# electronics_pom.net
KiCad netlist of a schematic drawn in EAGLE
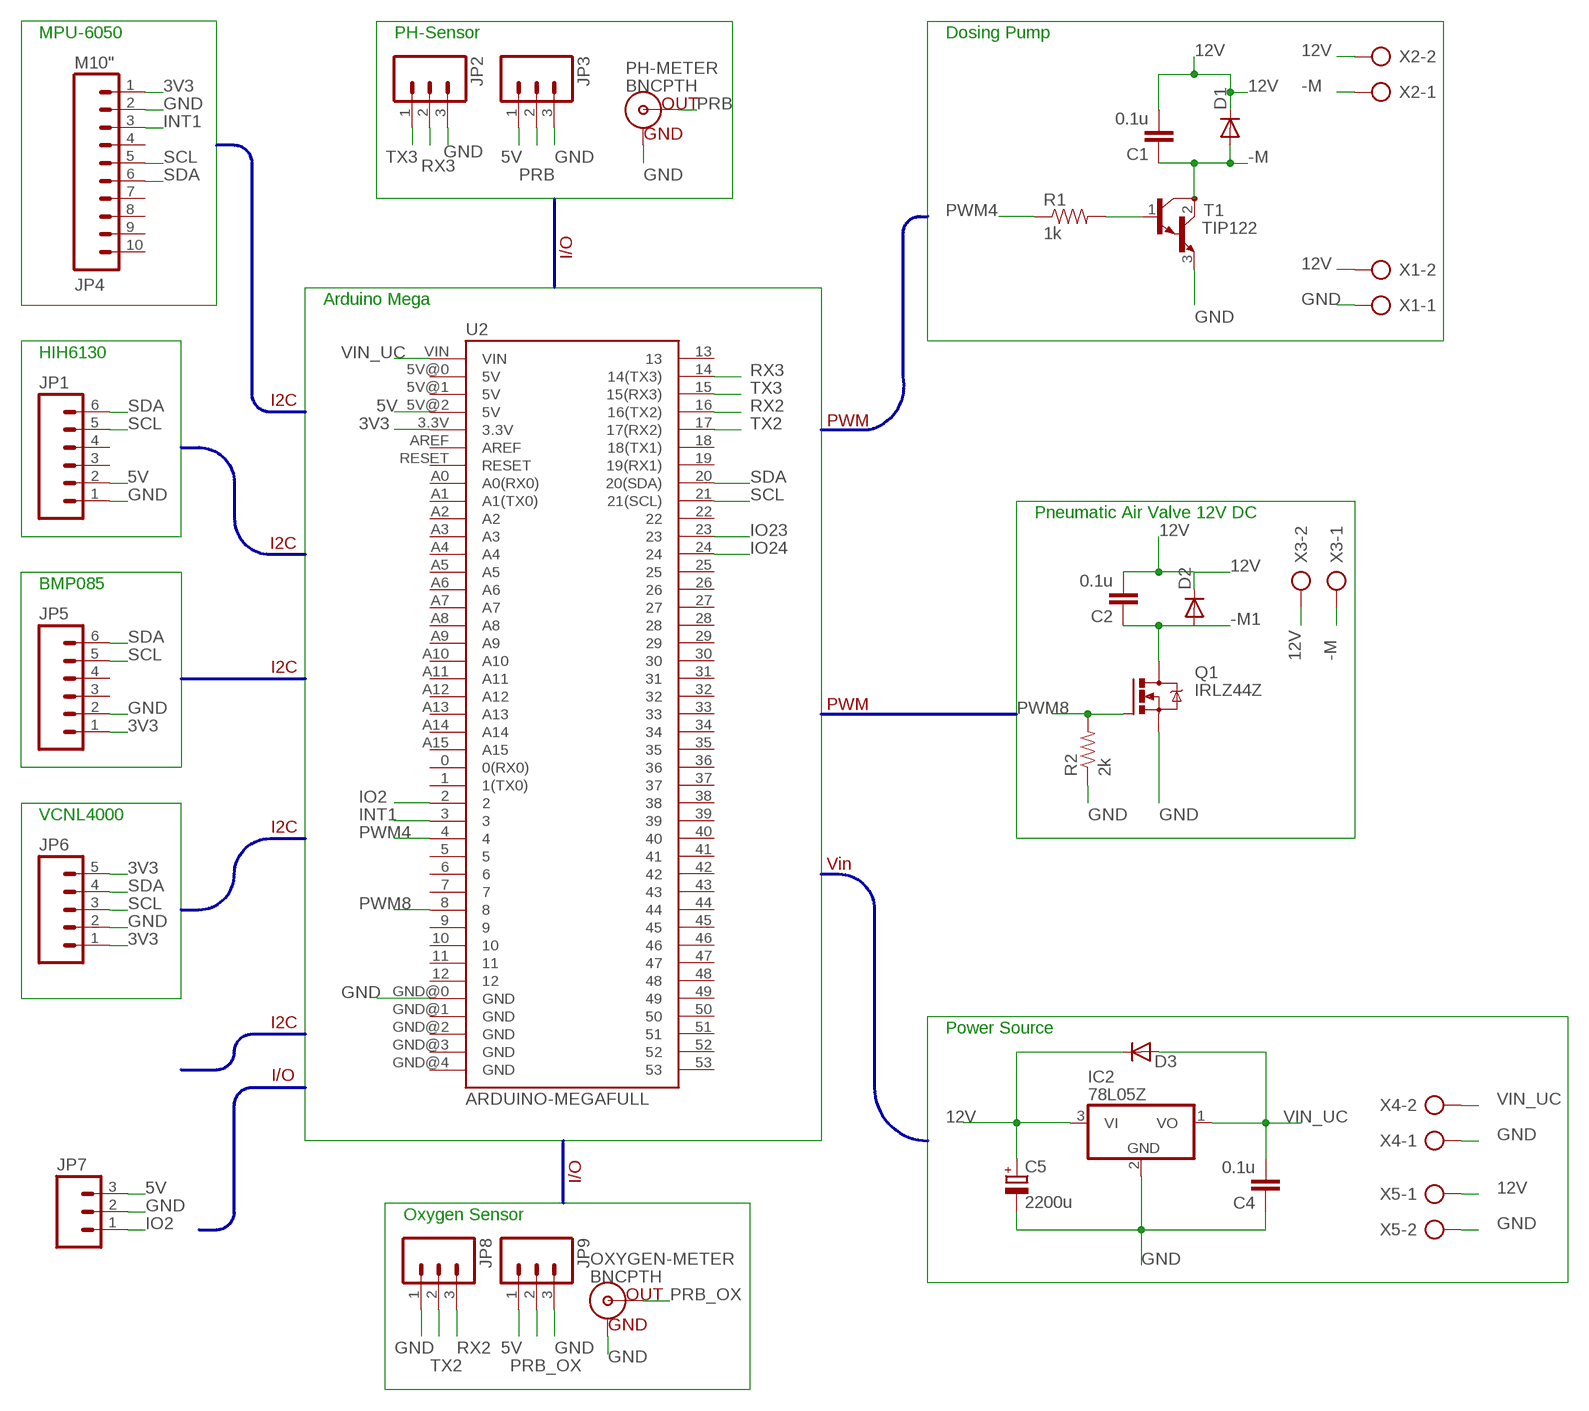
[diagram p0: schematic, sheet 1]

(export (version "E")
  (design (tool "Eeschema 10.0.6"))
  (components
    (comp (ref "C1")
      (value "0.1u")
      (footprint "eagle-import:CAP-PTH-SMALL")
      (libsource (lib "eagle-import") (part "CAPPTH"))
    )
    (comp (ref "C2")
      (value "0.1u")
      (footprint "eagle-import:CAP-PTH-SMALL")
      (libsource (lib "eagle-import") (part "CAPPTH"))
    )
    (comp (ref "C4")
      (value "0.1u")
      (footprint "eagle-import:CAP-PTH-SMALL")
      (libsource (lib "eagle-import") (part "CAPPTH"))
    )
    (comp (ref "C5")
      (value "2200u")
      (footprint "eagle-import:E5-13")
      (libsource (lib "eagle-import") (part "CPOL-EUE5-13"))
    )
    (comp (ref "D1")
      (value "DIODEPTH")
      (footprint "eagle-import:DIODE-1N4001")
      (libsource (lib "eagle-import") (part "DIODEPTH"))
    )
    (comp (ref "D2")
      (value "DIODEPTH")
      (footprint "eagle-import:DIODE-1N4001")
      (libsource (lib "eagle-import") (part "DIODEPTH"))
    )
    (comp (ref "D3")
      (value "DIODEPTH")
      (footprint "eagle-import:DIODE-1N4001")
      (libsource (lib "eagle-import") (part "DIODEPTH"))
    )
    (comp (ref "IC2")
      (value "78L05Z")
      (footprint "eagle-import:TO92")
      (libsource (lib "eagle-import") (part "78ZL05"))
    )
    (comp (ref "JP1")
      (value "M06LONGPADS")
      (footprint "eagle-import:1X06_LONGPADS")
      (libsource (lib "eagle-import") (part "M06LONGPADS"))
    )
    (comp (ref "JP2")
      (value "M03LONGPADS")
      (footprint "eagle-import:1X03_LONGPADS")
      (libsource (lib "eagle-import") (part "M03LONGPADS"))
    )
    (comp (ref "JP3")
      (value "M03LONGPADS")
      (footprint "eagle-import:1X03_LONGPADS")
      (libsource (lib "eagle-import") (part "M03LONGPADS"))
    )
    (comp (ref "JP4")
      (value "M10\"")
      (footprint "eagle-import:1X10")
      (libsource (lib "eagle-import") (part "M10{dblquote}"))
    )
    (comp (ref "JP5")
      (value "M06LONGPADS")
      (footprint "eagle-import:1X06_LONGPADS")
      (libsource (lib "eagle-import") (part "M06LONGPADS"))
    )
    (comp (ref "JP6")
      (value "M05PTH_LONGPADS")
      (footprint "eagle-import:1X05_LONGPADS")
      (libsource (lib "eagle-import") (part "M05PTH_LONGPADS"))
    )
    (comp (ref "JP7")
      (value "M03LONGPADS")
      (footprint "eagle-import:1X03_LONGPADS")
      (libsource (lib "eagle-import") (part "M03LONGPADS"))
    )
    (comp (ref "JP8")
      (value "M03LONGPADS")
      (footprint "eagle-import:1X03_LONGPADS")
      (libsource (lib "eagle-import") (part "M03LONGPADS"))
    )
    (comp (ref "JP9")
      (value "M03LONGPADS")
      (footprint "eagle-import:1X03_LONGPADS")
      (libsource (lib "eagle-import") (part "M03LONGPADS"))
    )
    (comp (ref "OXYGEN-METER")
      (value "BNCPTH")
      (footprint "eagle-import:BNC")
      (libsource (lib "eagle-import") (part "BNCPTH"))
    )
    (comp (ref "PH-METER")
      (value "BNCPTH")
      (footprint "eagle-import:BNC")
      (libsource (lib "eagle-import") (part "BNCPTH"))
    )
    (comp (ref "Q1")
      (value "IRLZ44Z")
      (footprint "eagle-import:TO220BH")
      (libsource (lib "eagle-import") (part "IRLZ44Z"))
    )
    (comp (ref "R1")
      (value "1k")
      (footprint "eagle-import:AXIAL-0.4")
      (libsource (lib "eagle-import") (part "RESISTORPTH-1/4W"))
    )
    (comp (ref "R2")
      (value "2k")
      (footprint "eagle-import:AXIAL-0.4")
      (libsource (lib "eagle-import") (part "RESISTORPTH-1/4W"))
    )
    (comp (ref "T1")
      (value "TIP122")
      (footprint "eagle-import:TO220")
      (libsource (lib "eagle-import") (part "TIP122"))
    )
    (comp (ref "U2")
      (value "ARDUINO-MEGAFULL")
      (footprint "eagle-import:ARDUINO_MEGA")
      (libsource (lib "eagle-import") (part "ARDUINO-MEGAFULL"))
    )
    (comp (ref "X1")
      (value "AK500/2")
      (footprint "eagle-import:AK500_2")
      (libsource (lib "eagle-import") (part "AK500/2"))
    )
    (comp (ref "X2")
      (value "AK500/2")
      (footprint "eagle-import:AK500_2")
      (libsource (lib "eagle-import") (part "AK500/2"))
    )
    (comp (ref "X3")
      (value "AK500/2")
      (footprint "eagle-import:AK500_2")
      (libsource (lib "eagle-import") (part "AK500/2"))
    )
    (comp (ref "X4")
      (value "AK500/2")
      (footprint "eagle-import:AK500_2")
      (libsource (lib "eagle-import") (part "AK500/2"))
    )
    (comp (ref "X5")
      (value "AK500/2")
      (footprint "eagle-import:AK500_2")
      (libsource (lib "eagle-import") (part "AK500/2"))
    )
  )
  (nets
    (net (code "1") (name "/-M") (class "Default")
      (node (ref "C1") (pin "1") (pinfunction "1_1") (pintype "passive"))
      (node (ref "D1") (pin "A") (pinfunction "A_A") (pintype "passive"))
      (node (ref "T1") (pin "2") (pinfunction "C_2") (pintype "passive"))
      (node (ref "X2") (pin "1") (pinfunction "KL_1") (pintype "passive"))
      (node (ref "X3") (pin "1") (pinfunction "KL_1") (pintype "passive"))
    )
    (net (code "2") (name "/-M1") (class "Default")
      (node (ref "C2") (pin "1") (pinfunction "1_1") (pintype "passive"))
      (node (ref "D2") (pin "A") (pinfunction "A_A") (pintype "passive"))
      (node (ref "Q1") (pin "D") (pinfunction "D_D") (pintype "passive"))
    )
    (net (code "3") (name "/3V3") (class "Default")
      (node (ref "JP4") (pin "1") (pinfunction "1_1") (pintype "passive"))
      (node (ref "JP5") (pin "1") (pinfunction "1_1") (pintype "passive"))
      (node (ref "JP6") (pin "1") (pinfunction "1_1") (pintype "passive"))
      (node (ref "JP6") (pin "5") (pinfunction "5_5") (pintype "passive"))
      (node (ref "U2") (pin "3.3V") (pinfunction "3.3V_3.3V") (pintype "bidirectional"))
    )
    (net (code "4") (name "/5V") (class "Default")
      (node (ref "JP1") (pin "2") (pinfunction "2_2") (pintype "passive"))
      (node (ref "JP3") (pin "1") (pinfunction "1_1") (pintype "passive"))
      (node (ref "JP7") (pin "3") (pinfunction "3_3") (pintype "passive"))
      (node (ref "JP9") (pin "1") (pinfunction "1_1") (pintype "passive"))
      (node (ref "U2") (pin "5V@2") (pinfunction "5V_5V@2") (pintype "bidirectional"))
    )
    (net (code "5") (name "/12V") (class "Default")
      (node (ref "C1") (pin "2") (pinfunction "2_2") (pintype "passive"))
      (node (ref "C2") (pin "2") (pinfunction "2_2") (pintype "passive"))
      (node (ref "C5") (pin "+") (pinfunction "+_+") (pintype "passive"))
      (node (ref "D1") (pin "C") (pinfunction "C_C") (pintype "passive"))
      (node (ref "D2") (pin "C") (pinfunction "C_C") (pintype "passive"))
      (node (ref "D3") (pin "C") (pinfunction "C_C") (pintype "passive"))
      (node (ref "IC2") (pin "3") (pinfunction "VI_3") (pintype "input"))
      (node (ref "X1") (pin "2") (pinfunction "KL_2") (pintype "passive"))
      (node (ref "X2") (pin "2") (pinfunction "KL_2") (pintype "passive"))
      (node (ref "X3") (pin "2") (pinfunction "KL_2") (pintype "passive"))
      (node (ref "X5") (pin "1") (pinfunction "KL_1") (pintype "passive"))
    )
    (net (code "6") (name "/GND") (class "Default")
      (node (ref "C4") (pin "1") (pinfunction "1_1") (pintype "passive"))
      (node (ref "C5") (pin "-") (pinfunction "-_-") (pintype "passive"))
      (node (ref "IC2") (pin "2") (pinfunction "GND_2") (pintype "passive"))
      (node (ref "JP1") (pin "1") (pinfunction "1_1") (pintype "passive"))
      (node (ref "JP2") (pin "3") (pinfunction "3_3") (pintype "passive"))
      (node (ref "JP3") (pin "3") (pinfunction "3_3") (pintype "passive"))
      (node (ref "JP4") (pin "2") (pinfunction "2_2") (pintype "passive"))
      (node (ref "JP5") (pin "2") (pinfunction "2_2") (pintype "passive"))
      (node (ref "JP6") (pin "2") (pinfunction "2_2") (pintype "passive"))
      (node (ref "JP7") (pin "2") (pinfunction "2_2") (pintype "passive"))
      (node (ref "JP8") (pin "1") (pinfunction "1_1") (pintype "passive"))
      (node (ref "JP9") (pin "3") (pinfunction "3_3") (pintype "passive"))
      (node (ref "OXYGEN-METER") (pin "GND") (pinfunction "GND_GND") (pintype "bidirectional"))
      (node (ref "PH-METER") (pin "GND") (pinfunction "GND_GND") (pintype "bidirectional"))
      (node (ref "Q1") (pin "S") (pinfunction "S_S") (pintype "passive"))
      (node (ref "R2") (pin "P$1") (pinfunction "1_P$1") (pintype "passive"))
      (node (ref "T1") (pin "3") (pinfunction "E_3") (pintype "passive"))
      (node (ref "U2") (pin "GND@0") (pinfunction "GND_GND@0") (pintype "bidirectional"))
      (node (ref "X1") (pin "1") (pinfunction "KL_1") (pintype "passive"))
      (node (ref "X4") (pin "1") (pinfunction "KL_1") (pintype "passive"))
      (node (ref "X5") (pin "2") (pinfunction "KL_2") (pintype "passive"))
    )
    (net (code "7") (name "/INT1") (class "Default")
      (node (ref "JP4") (pin "3") (pinfunction "3_3") (pintype "passive"))
      (node (ref "U2") (pin "3") (pinfunction "3_3") (pintype "bidirectional"))
    )
    (net (code "8") (name "/IO2") (class "Default")
      (node (ref "JP7") (pin "1") (pinfunction "1_1") (pintype "passive"))
      (node (ref "U2") (pin "2") (pinfunction "2_2") (pintype "bidirectional"))
    )
    (net (code "9") (name "/IO23") (class "Default")
      (node (ref "U2") (pin "23") (pinfunction "23_23") (pintype "bidirectional"))
    )
    (net (code "10") (name "/IO24") (class "Default")
      (node (ref "U2") (pin "24") (pinfunction "24_24") (pintype "bidirectional"))
    )
    (net (code "11") (name "/PRB") (class "Default")
      (node (ref "JP3") (pin "2") (pinfunction "2_2") (pintype "passive"))
      (node (ref "PH-METER") (pin "S") (pinfunction "OUT_S") (pintype "bidirectional"))
    )
    (net (code "12") (name "/PRB_OX") (class "Default")
      (node (ref "JP9") (pin "2") (pinfunction "2_2") (pintype "passive"))
      (node (ref "OXYGEN-METER") (pin "S") (pinfunction "OUT_S") (pintype "bidirectional"))
    )
    (net (code "13") (name "/PWM4") (class "Default")
      (node (ref "R1") (pin "P$1") (pinfunction "1_P$1") (pintype "passive"))
      (node (ref "U2") (pin "4") (pinfunction "4_4") (pintype "bidirectional"))
    )
    (net (code "14") (name "/PWM8") (class "Default")
      (node (ref "Q1") (pin "G") (pinfunction "G_G") (pintype "passive"))
      (node (ref "R2") (pin "P$2") (pinfunction "2_P$2") (pintype "passive"))
      (node (ref "U2") (pin "8") (pinfunction "8_8") (pintype "bidirectional"))
    )
    (net (code "15") (name "/RX2") (class "Default")
      (node (ref "JP8") (pin "3") (pinfunction "3_3") (pintype "passive"))
      (node (ref "U2") (pin "16") (pinfunction "16(TX2)_16") (pintype "bidirectional"))
    )
    (net (code "16") (name "/RX3") (class "Default")
      (node (ref "JP2") (pin "2") (pinfunction "2_2") (pintype "passive"))
      (node (ref "U2") (pin "14") (pinfunction "14(TX3)_14") (pintype "bidirectional"))
    )
    (net (code "17") (name "/SCL") (class "Default")
      (node (ref "JP1") (pin "5") (pinfunction "5_5") (pintype "passive"))
      (node (ref "JP4") (pin "5") (pinfunction "5_5") (pintype "passive"))
      (node (ref "JP5") (pin "5") (pinfunction "5_5") (pintype "passive"))
      (node (ref "JP6") (pin "3") (pinfunction "3_3") (pintype "passive"))
      (node (ref "U2") (pin "21") (pinfunction "21(SCL)_21") (pintype "bidirectional"))
    )
    (net (code "18") (name "/SDA") (class "Default")
      (node (ref "JP1") (pin "6") (pinfunction "6_6") (pintype "passive"))
      (node (ref "JP4") (pin "6") (pinfunction "6_6") (pintype "passive"))
      (node (ref "JP5") (pin "6") (pinfunction "6_6") (pintype "passive"))
      (node (ref "JP6") (pin "4") (pinfunction "4_4") (pintype "passive"))
      (node (ref "U2") (pin "20") (pinfunction "20(SDA)_20") (pintype "bidirectional"))
    )
    (net (code "19") (name "/TX2") (class "Default")
      (node (ref "JP8") (pin "2") (pinfunction "2_2") (pintype "passive"))
      (node (ref "U2") (pin "17") (pinfunction "17(RX2)_17") (pintype "bidirectional"))
    )
    (net (code "20") (name "/TX3") (class "Default")
      (node (ref "JP2") (pin "1") (pinfunction "1_1") (pintype "passive"))
      (node (ref "U2") (pin "15") (pinfunction "15(RX3)_15") (pintype "bidirectional"))
    )
    (net (code "21") (name "/VIN_UC") (class "Default")
      (node (ref "C4") (pin "2") (pinfunction "2_2") (pintype "passive"))
      (node (ref "D3") (pin "A") (pinfunction "A_A") (pintype "passive"))
      (node (ref "IC2") (pin "1") (pinfunction "VO_1") (pintype "passive"))
      (node (ref "U2") (pin "VIN") (pinfunction "VIN_VIN") (pintype "bidirectional"))
      (node (ref "X4") (pin "2") (pinfunction "KL_2") (pintype "passive"))
    )
    (net (code "22") (name "Net-(R1-2)") (class "Default")
      (node (ref "R1") (pin "P$2") (pinfunction "2_P$2") (pintype "passive"))
      (node (ref "T1") (pin "1") (pinfunction "B_1") (pintype "passive"))
    )
    (net (code "23") (name "unconnected-(JP1-Pad3)") (class "Default")
      (node (ref "JP1") (pin "3") (pinfunction "3_3") (pintype "passive"))
    )
    (net (code "24") (name "unconnected-(JP1-Pad4)") (class "Default")
      (node (ref "JP1") (pin "4") (pinfunction "4_4") (pintype "passive"))
    )
    (net (code "25") (name "unconnected-(JP4-Pad4)") (class "Default")
      (node (ref "JP4") (pin "4") (pinfunction "4_4") (pintype "passive"))
    )
    (net (code "26") (name "unconnected-(JP4-Pad7)") (class "Default")
      (node (ref "JP4") (pin "7") (pinfunction "7_7") (pintype "passive"))
    )
    (net (code "27") (name "unconnected-(JP4-Pad8)") (class "Default")
      (node (ref "JP4") (pin "8") (pinfunction "8_8") (pintype "passive"))
    )
    (net (code "28") (name "unconnected-(JP4-Pad9)") (class "Default")
      (node (ref "JP4") (pin "9") (pinfunction "9_9") (pintype "passive"))
    )
    (net (code "29") (name "unconnected-(JP4-Pad10)") (class "Default")
      (node (ref "JP4") (pin "10") (pinfunction "10_10") (pintype "passive"))
    )
    (net (code "30") (name "unconnected-(JP5-Pad3)") (class "Default")
      (node (ref "JP5") (pin "3") (pinfunction "3_3") (pintype "passive"))
    )
    (net (code "31") (name "unconnected-(JP5-Pad4)") (class "Default")
      (node (ref "JP5") (pin "4") (pinfunction "4_4") (pintype "passive"))
    )
    (net (code "32") (name "unconnected-(U2-0(RX0)-Pad0)") (class "Default")
      (node (ref "U2") (pin "0") (pinfunction "0(RX0)_0") (pintype "bidirectional"))
    )
    (net (code "33") (name "unconnected-(U2-1(TX0)-Pad1)") (class "Default")
      (node (ref "U2") (pin "1") (pinfunction "1(TX0)_1") (pintype "bidirectional"))
    )
    (net (code "34") (name "unconnected-(U2-5V-Pad5V@0)") (class "Default")
      (node (ref "U2") (pin "5V@0") (pinfunction "5V_5V@0") (pintype "bidirectional"))
    )
    (net (code "35") (name "unconnected-(U2-5V-Pad5V@1)") (class "Default")
      (node (ref "U2") (pin "5V@1") (pinfunction "5V_5V@1") (pintype "bidirectional"))
    )
    (net (code "36") (name "unconnected-(U2-18(TX1)-Pad18)") (class "Default")
      (node (ref "U2") (pin "18") (pinfunction "18(TX1)_18") (pintype "bidirectional"))
    )
    (net (code "37") (name "unconnected-(U2-19(RX1)-Pad19)") (class "Default")
      (node (ref "U2") (pin "19") (pinfunction "19(RX1)_19") (pintype "bidirectional"))
    )
    (net (code "38") (name "unconnected-(U2-A0(RX0)-PadA0)") (class "Default")
      (node (ref "U2") (pin "A0") (pinfunction "A0(RX0)_A0") (pintype "bidirectional"))
    )
    (net (code "39") (name "unconnected-(U2-A1(TX0)-PadA1)") (class "Default")
      (node (ref "U2") (pin "A1") (pinfunction "A1(TX0)_A1") (pintype "bidirectional"))
    )
    (net (code "40") (name "unconnected-(U2-GND-PadGND@1)") (class "Default")
      (node (ref "U2") (pin "GND@1") (pinfunction "GND_GND@1") (pintype "bidirectional"))
    )
    (net (code "41") (name "unconnected-(U2-GND-PadGND@2)") (class "Default")
      (node (ref "U2") (pin "GND@2") (pinfunction "GND_GND@2") (pintype "bidirectional"))
    )
    (net (code "42") (name "unconnected-(U2-GND-PadGND@3)") (class "Default")
      (node (ref "U2") (pin "GND@3") (pinfunction "GND_GND@3") (pintype "bidirectional"))
    )
    (net (code "43") (name "unconnected-(U2-GND-PadGND@4)") (class "Default")
      (node (ref "U2") (pin "GND@4") (pinfunction "GND_GND@4") (pintype "bidirectional"))
    )
    (net (code "44") (name "unconnected-(U2-Pad5)") (class "Default")
      (node (ref "U2") (pin "5") (pinfunction "5_5") (pintype "bidirectional"))
    )
    (net (code "45") (name "unconnected-(U2-Pad6)") (class "Default")
      (node (ref "U2") (pin "6") (pinfunction "6_6") (pintype "bidirectional"))
    )
    (net (code "46") (name "unconnected-(U2-Pad7)") (class "Default")
      (node (ref "U2") (pin "7") (pinfunction "7_7") (pintype "bidirectional"))
    )
    (net (code "47") (name "unconnected-(U2-Pad9)") (class "Default")
      (node (ref "U2") (pin "9") (pinfunction "9_9") (pintype "bidirectional"))
    )
    (net (code "48") (name "unconnected-(U2-Pad10)") (class "Default")
      (node (ref "U2") (pin "10") (pinfunction "10_10") (pintype "bidirectional"))
    )
    (net (code "49") (name "unconnected-(U2-Pad11)") (class "Default")
      (node (ref "U2") (pin "11") (pinfunction "11_11") (pintype "bidirectional"))
    )
    (net (code "50") (name "unconnected-(U2-Pad12)") (class "Default")
      (node (ref "U2") (pin "12") (pinfunction "12_12") (pintype "bidirectional"))
    )
    (net (code "51") (name "unconnected-(U2-Pad13)") (class "Default")
      (node (ref "U2") (pin "13") (pinfunction "13_13") (pintype "bidirectional"))
    )
    (net (code "52") (name "unconnected-(U2-Pad22)") (class "Default")
      (node (ref "U2") (pin "22") (pinfunction "22_22") (pintype "bidirectional"))
    )
    (net (code "53") (name "unconnected-(U2-Pad25)") (class "Default")
      (node (ref "U2") (pin "25") (pinfunction "25_25") (pintype "bidirectional"))
    )
    (net (code "54") (name "unconnected-(U2-Pad26)") (class "Default")
      (node (ref "U2") (pin "26") (pinfunction "26_26") (pintype "bidirectional"))
    )
    (net (code "55") (name "unconnected-(U2-Pad27)") (class "Default")
      (node (ref "U2") (pin "27") (pinfunction "27_27") (pintype "bidirectional"))
    )
    (net (code "56") (name "unconnected-(U2-Pad28)") (class "Default")
      (node (ref "U2") (pin "28") (pinfunction "28_28") (pintype "bidirectional"))
    )
    (net (code "57") (name "unconnected-(U2-Pad29)") (class "Default")
      (node (ref "U2") (pin "29") (pinfunction "29_29") (pintype "bidirectional"))
    )
    (net (code "58") (name "unconnected-(U2-Pad30)") (class "Default")
      (node (ref "U2") (pin "30") (pinfunction "30_30") (pintype "bidirectional"))
    )
    (net (code "59") (name "unconnected-(U2-Pad31)") (class "Default")
      (node (ref "U2") (pin "31") (pinfunction "31_31") (pintype "bidirectional"))
    )
    (net (code "60") (name "unconnected-(U2-Pad32)") (class "Default")
      (node (ref "U2") (pin "32") (pinfunction "32_32") (pintype "bidirectional"))
    )
    (net (code "61") (name "unconnected-(U2-Pad33)") (class "Default")
      (node (ref "U2") (pin "33") (pinfunction "33_33") (pintype "bidirectional"))
    )
    (net (code "62") (name "unconnected-(U2-Pad34)") (class "Default")
      (node (ref "U2") (pin "34") (pinfunction "34_34") (pintype "bidirectional"))
    )
    (net (code "63") (name "unconnected-(U2-Pad35)") (class "Default")
      (node (ref "U2") (pin "35") (pinfunction "35_35") (pintype "bidirectional"))
    )
    (net (code "64") (name "unconnected-(U2-Pad36)") (class "Default")
      (node (ref "U2") (pin "36") (pinfunction "36_36") (pintype "bidirectional"))
    )
    (net (code "65") (name "unconnected-(U2-Pad37)") (class "Default")
      (node (ref "U2") (pin "37") (pinfunction "37_37") (pintype "bidirectional"))
    )
    (net (code "66") (name "unconnected-(U2-Pad38)") (class "Default")
      (node (ref "U2") (pin "38") (pinfunction "38_38") (pintype "bidirectional"))
    )
    (net (code "67") (name "unconnected-(U2-Pad39)") (class "Default")
      (node (ref "U2") (pin "39") (pinfunction "39_39") (pintype "bidirectional"))
    )
    (net (code "68") (name "unconnected-(U2-Pad40)") (class "Default")
      (node (ref "U2") (pin "40") (pinfunction "40_40") (pintype "bidirectional"))
    )
    (net (code "69") (name "unconnected-(U2-Pad41)") (class "Default")
      (node (ref "U2") (pin "41") (pinfunction "41_41") (pintype "bidirectional"))
    )
    (net (code "70") (name "unconnected-(U2-Pad42)") (class "Default")
      (node (ref "U2") (pin "42") (pinfunction "42_42") (pintype "bidirectional"))
    )
    (net (code "71") (name "unconnected-(U2-Pad43)") (class "Default")
      (node (ref "U2") (pin "43") (pinfunction "43_43") (pintype "bidirectional"))
    )
    (net (code "72") (name "unconnected-(U2-Pad44)") (class "Default")
      (node (ref "U2") (pin "44") (pinfunction "44_44") (pintype "bidirectional"))
    )
    (net (code "73") (name "unconnected-(U2-Pad45)") (class "Default")
      (node (ref "U2") (pin "45") (pinfunction "45_45") (pintype "bidirectional"))
    )
    (net (code "74") (name "unconnected-(U2-Pad46)") (class "Default")
      (node (ref "U2") (pin "46") (pinfunction "46_46") (pintype "bidirectional"))
    )
    (net (code "75") (name "unconnected-(U2-Pad47)") (class "Default")
      (node (ref "U2") (pin "47") (pinfunction "47_47") (pintype "bidirectional"))
    )
    (net (code "76") (name "unconnected-(U2-Pad48)") (class "Default")
      (node (ref "U2") (pin "48") (pinfunction "48_48") (pintype "bidirectional"))
    )
    (net (code "77") (name "unconnected-(U2-Pad49)") (class "Default")
      (node (ref "U2") (pin "49") (pinfunction "49_49") (pintype "bidirectional"))
    )
    (net (code "78") (name "unconnected-(U2-Pad50)") (class "Default")
      (node (ref "U2") (pin "50") (pinfunction "50_50") (pintype "bidirectional"))
    )
    (net (code "79") (name "unconnected-(U2-Pad51)") (class "Default")
      (node (ref "U2") (pin "51") (pinfunction "51_51") (pintype "bidirectional"))
    )
    (net (code "80") (name "unconnected-(U2-Pad52)") (class "Default")
      (node (ref "U2") (pin "52") (pinfunction "52_52") (pintype "bidirectional"))
    )
    (net (code "81") (name "unconnected-(U2-Pad53)") (class "Default")
      (node (ref "U2") (pin "53") (pinfunction "53_53") (pintype "bidirectional"))
    )
    (net (code "82") (name "unconnected-(U2-PadA2)") (class "Default")
      (node (ref "U2") (pin "A2") (pinfunction "A2_A2") (pintype "bidirectional"))
    )
    (net (code "83") (name "unconnected-(U2-PadA3)") (class "Default")
      (node (ref "U2") (pin "A3") (pinfunction "A3_A3") (pintype "bidirectional"))
    )
    (net (code "84") (name "unconnected-(U2-PadA4)") (class "Default")
      (node (ref "U2") (pin "A4") (pinfunction "A4_A4") (pintype "bidirectional"))
    )
    (net (code "85") (name "unconnected-(U2-PadA5)") (class "Default")
      (node (ref "U2") (pin "A5") (pinfunction "A5_A5") (pintype "bidirectional"))
    )
    (net (code "86") (name "unconnected-(U2-PadA6)") (class "Default")
      (node (ref "U2") (pin "A6") (pinfunction "A6_A6") (pintype "bidirectional"))
    )
    (net (code "87") (name "unconnected-(U2-PadA7)") (class "Default")
      (node (ref "U2") (pin "A7") (pinfunction "A7_A7") (pintype "bidirectional"))
    )
    (net (code "88") (name "unconnected-(U2-PadA8)") (class "Default")
      (node (ref "U2") (pin "A8") (pinfunction "A8_A8") (pintype "bidirectional"))
    )
    (net (code "89") (name "unconnected-(U2-PadA9)") (class "Default")
      (node (ref "U2") (pin "A9") (pinfunction "A9_A9") (pintype "bidirectional"))
    )
    (net (code "90") (name "unconnected-(U2-PadA10)") (class "Default")
      (node (ref "U2") (pin "A10") (pinfunction "A10_A10") (pintype "bidirectional"))
    )
    (net (code "91") (name "unconnected-(U2-PadA11)") (class "Default")
      (node (ref "U2") (pin "A11") (pinfunction "A11_A11") (pintype "bidirectional"))
    )
    (net (code "92") (name "unconnected-(U2-PadA12)") (class "Default")
      (node (ref "U2") (pin "A12") (pinfunction "A12_A12") (pintype "bidirectional"))
    )
    (net (code "93") (name "unconnected-(U2-PadA13)") (class "Default")
      (node (ref "U2") (pin "A13") (pinfunction "A13_A13") (pintype "bidirectional"))
    )
    (net (code "94") (name "unconnected-(U2-PadA14)") (class "Default")
      (node (ref "U2") (pin "A14") (pinfunction "A14_A14") (pintype "bidirectional"))
    )
    (net (code "95") (name "unconnected-(U2-PadA15)") (class "Default")
      (node (ref "U2") (pin "A15") (pinfunction "A15_A15") (pintype "bidirectional"))
    )
    (net (code "96") (name "unconnected-(U2-PadAREF)") (class "Default")
      (node (ref "U2") (pin "AREF") (pinfunction "AREF_AREF") (pintype "bidirectional"))
    )
    (net (code "97") (name "unconnected-(U2-PadRESET)") (class "Default")
      (node (ref "U2") (pin "RESET") (pinfunction "RESET_RESET") (pintype "bidirectional"))
    )
  )
)
